# Data_Process_System.net
KiCad netlist of a schematic drawn in Altium Designer
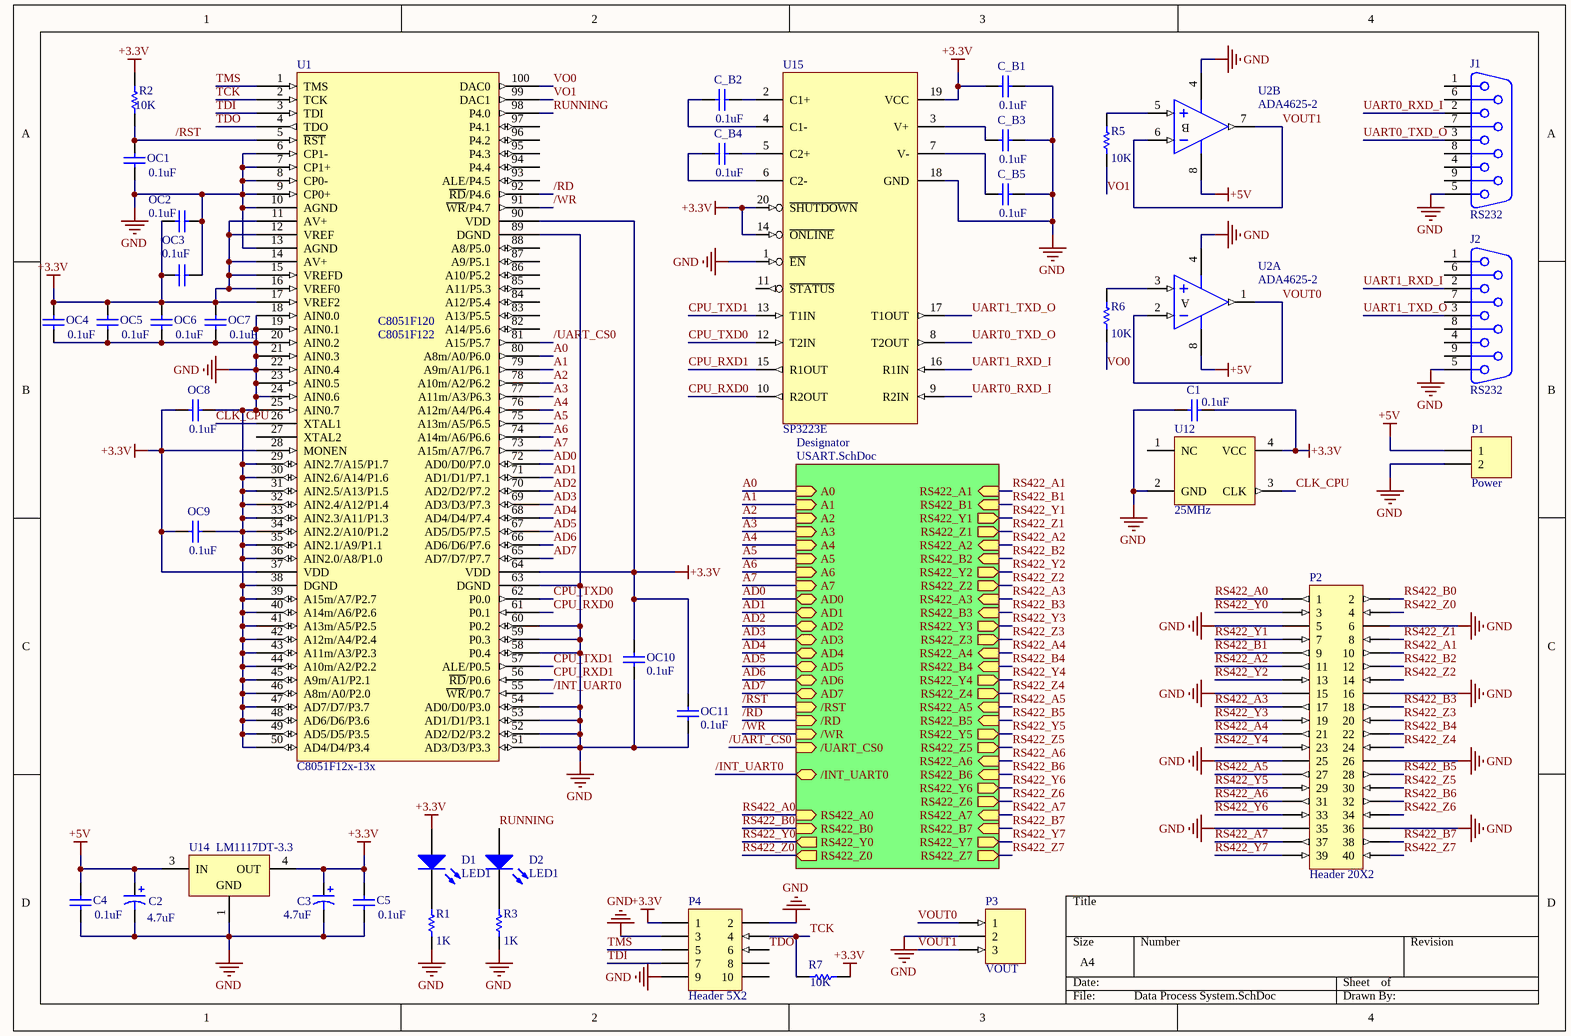
[diagram p0: Data Process System.SchDoc]

(export (version "E")
  (design (tool "Eeschema 10.0.6"))
  (components
    (comp (ref "C1")
      (value "0.1uF")
      (footprint "0805")
      (description "Capacitor")
      (fields (field (name "Comment") "Cap 0.1uf") (field (name "PUBLISHER") "Altium Limited"))
      (libsource (lib "Miscellaneous Devices") (part "Cap"))
    )
    (comp (ref "C2")
      (value "4.7uF")
      (footprint "3528")
      (description "Polarized Capacitor (Surface Mount)")
      (fields (field (name "Comment") "Cap Pol 4.7uf") (field (name "PUBLISHER") "Altium Limited"))
      (libsource (lib "Miscellaneous Devices") (part "Cap Pol3"))
    )
    (comp (ref "C3")
      (value "4.7uF")
      (footprint "3528")
      (description "Polarized Capacitor (Surface Mount)")
      (fields (field (name "Comment") "Cap Pol 4.7uf") (field (name "PUBLISHER") "Altium Limited"))
      (libsource (lib "Miscellaneous Devices") (part "Cap Pol3"))
    )
    (comp (ref "C4")
      (value "0.1uF")
      (footprint "0805")
      (description "Capacitor")
      (fields (field (name "Comment") "Cap 0.1uf") (field (name "PUBLISHER") "Altium Limited"))
      (libsource (lib "Miscellaneous Devices") (part "Cap"))
    )
    (comp (ref "C5")
      (value "0.1uF")
      (footprint "0805")
      (description "Capacitor")
      (fields (field (name "Comment") "Cap 0.1uf") (field (name "PUBLISHER") "Altium Limited"))
      (libsource (lib "Miscellaneous Devices") (part "Cap"))
    )
    (comp (ref "C_B1")
      (value "0.1uF")
      (footprint "0805")
      (description "Capacitor")
      (fields (field (name "Comment") "Cap 0.1uf") (field (name "PUBLISHER") "Altium Limited"))
      (libsource (lib "Miscellaneous Devices") (part "Cap"))
    )
    (comp (ref "C_B2")
      (value "0.1uF")
      (footprint "0805")
      (description "Capacitor")
      (fields (field (name "Comment") "Cap 0.1uf") (field (name "PUBLISHER") "Altium Limited"))
      (libsource (lib "Miscellaneous Devices") (part "Cap"))
    )
    (comp (ref "C_B3")
      (value "0.1uF")
      (footprint "0805")
      (description "Capacitor")
      (fields (field (name "Comment") "Cap 0.1uf") (field (name "PUBLISHER") "Altium Limited"))
      (libsource (lib "Miscellaneous Devices") (part "Cap"))
    )
    (comp (ref "C_B4")
      (value "0.1uF")
      (footprint "0805")
      (description "Capacitor")
      (fields (field (name "Comment") "Cap 0.1uf") (field (name "PUBLISHER") "Altium Limited"))
      (libsource (lib "Miscellaneous Devices") (part "Cap"))
    )
    (comp (ref "C_B5")
      (value "0.1uF")
      (footprint "0805")
      (description "Capacitor")
      (fields (field (name "Comment") "Cap 0.1uf") (field (name "PUBLISHER") "Altium Limited"))
      (libsource (lib "Miscellaneous Devices") (part "Cap"))
    )
    (comp (ref "D1")
      (value "LED1")
      (footprint "3216")
      (description "Typical RED GaAs LED")
      (fields (field (name "PUBLISHER") "Altium Limited"))
      (libsource (lib "Miscellaneous Devices") (part "LED1"))
    )
    (comp (ref "D2")
      (value "LED1")
      (footprint "3216")
      (description "Typical RED GaAs LED")
      (fields (field (name "PUBLISHER") "Altium Limited"))
      (libsource (lib "Miscellaneous Devices") (part "LED1"))
    )
    (comp (ref "J1")
      (value "RS232")
      (footprint "DSUB1.385-2H9")
      (description "Receptacle Assembly, 9 Position, Right Angle")
      (fields (field (name "PUBLISHER") "Altium Limited"))
      (libsource (lib "Miscellaneous Connectors") (part "D Connector 9"))
    )
    (comp (ref "J2")
      (value "RS232")
      (footprint "DSUB1.385-2H9")
      (description "Receptacle Assembly, 9 Position, Right Angle")
      (fields (field (name "PUBLISHER") "Altium Limited"))
      (libsource (lib "Miscellaneous Connectors") (part "D Connector 9"))
    )
    (comp (ref "OC1")
      (value "0.1uF")
      (footprint "0805")
      (description "Capacitor")
      (fields (field (name "Comment") "Cap 0.1uf") (field (name "PUBLISHER") "Altium Limited"))
      (libsource (lib "Miscellaneous Devices") (part "Cap"))
    )
    (comp (ref "OC2")
      (value "0.1uF")
      (footprint "0805")
      (description "Capacitor")
      (fields (field (name "Comment") "Cap 0.1uf") (field (name "PUBLISHER") "Altium Limited"))
      (libsource (lib "Miscellaneous Devices") (part "Cap"))
    )
    (comp (ref "OC3")
      (value "0.1uF")
      (footprint "0805")
      (description "Capacitor")
      (fields (field (name "Comment") "Cap 0.1uf") (field (name "PUBLISHER") "Altium Limited"))
      (libsource (lib "Miscellaneous Devices") (part "Cap"))
    )
    (comp (ref "OC4")
      (value "0.1uF")
      (footprint "0805")
      (description "Capacitor")
      (fields (field (name "Comment") "Cap 0.1uf") (field (name "PUBLISHER") "Altium Limited"))
      (libsource (lib "Miscellaneous Devices") (part "Cap"))
    )
    (comp (ref "OC5")
      (value "0.1uF")
      (footprint "0805")
      (description "Capacitor")
      (fields (field (name "Comment") "Cap 0.1uf") (field (name "PUBLISHER") "Altium Limited"))
      (libsource (lib "Miscellaneous Devices") (part "Cap"))
    )
    (comp (ref "OC6")
      (value "0.1uF")
      (footprint "0805")
      (description "Capacitor")
      (fields (field (name "Comment") "Cap 0.1uf") (field (name "PUBLISHER") "Altium Limited"))
      (libsource (lib "Miscellaneous Devices") (part "Cap"))
    )
    (comp (ref "OC7")
      (value "0.1uF")
      (footprint "0805")
      (description "Capacitor")
      (fields (field (name "Comment") "Cap 0.1uf") (field (name "PUBLISHER") "Altium Limited"))
      (libsource (lib "Miscellaneous Devices") (part "Cap"))
    )
    (comp (ref "OC8")
      (value "0.1uF")
      (footprint "0805")
      (description "Capacitor")
      (fields (field (name "Comment") "Cap 0.1uf") (field (name "PUBLISHER") "Altium Limited"))
      (libsource (lib "Miscellaneous Devices") (part "Cap"))
    )
    (comp (ref "OC9")
      (value "0.1uF")
      (footprint "0805")
      (description "Capacitor")
      (fields (field (name "Comment") "Cap 0.1uf") (field (name "PUBLISHER") "Altium Limited"))
      (libsource (lib "Miscellaneous Devices") (part "Cap"))
    )
    (comp (ref "OC10")
      (value "0.1uF")
      (footprint "0805")
      (description "Capacitor")
      (fields (field (name "Comment") "Cap 0.1uf") (field (name "PUBLISHER") "Altium Limited"))
      (libsource (lib "Miscellaneous Devices") (part "Cap"))
    )
    (comp (ref "OC11")
      (value "0.1uF")
      (footprint "0805")
      (description "Capacitor")
      (fields (field (name "Comment") "Cap 0.1uf") (field (name "PUBLISHER") "Altium Limited"))
      (libsource (lib "Miscellaneous Devices") (part "Cap"))
    )
    (comp (ref "P1")
      (value "Power")
      (footprint "HDR1X2")
      (description "Header, 2-Pin")
      (fields (field (name "PUBLISHER") "Altium Limited"))
      (libsource (lib "Miscellaneous Connectors") (part "Header 2"))
    )
    (comp (ref "P2")
      (value "Header 20X2")
      (footprint "HDR2X20")
      (description "Header, 20-Pin, Dual row")
      (fields (field (name "PUBLISHER") "Altium Limited"))
      (libsource (lib "Miscellaneous Connectors") (part "Header 20X2"))
    )
    (comp (ref "P3")
      (value "VOUT")
      (footprint "HDR1X3")
      (description "Header, 3-Pin")
      (fields (field (name "PUBLISHER") "Altium Limited"))
      (libsource (lib "Miscellaneous Connectors") (part "Header 3"))
    )
    (comp (ref "P4")
      (value "Header 5X2")
      (footprint "HDR2X5")
      (description "Header, 5-Pin, Dual row")
      (fields (field (name "PUBLISHER") "Altium Limited"))
      (libsource (lib "Miscellaneous Connectors") (part "Header 5X2"))
    )
    (comp (ref "R1")
      (value "1K")
      (footprint "0805")
      (description "Resistor")
      (fields (field (name "Comment") "1k") (field (name "PUBLISHER") "Altium Limited"))
      (libsource (lib "Miscellaneous Devices") (part "Res1"))
    )
    (comp (ref "R2")
      (value "10K")
      (footprint "0805")
      (description "Resistor")
      (fields (field (name "Comment") "10k") (field (name "PUBLISHER") "Altium Limited"))
      (libsource (lib "Miscellaneous Devices") (part "Res1"))
    )
    (comp (ref "R3")
      (value "1K")
      (footprint "0805")
      (description "Resistor")
      (fields (field (name "Comment") "1k") (field (name "PUBLISHER") "Altium Limited"))
      (libsource (lib "Miscellaneous Devices") (part "Res1"))
    )
    (comp (ref "R5")
      (value "10K")
      (footprint "0805")
      (description "Resistor")
      (fields (field (name "Comment") "10k") (field (name "PUBLISHER") "Altium Limited"))
      (libsource (lib "Miscellaneous Devices") (part "Res1"))
    )
    (comp (ref "R6")
      (value "10K")
      (footprint "0805")
      (description "Resistor")
      (fields (field (name "Comment") "10k") (field (name "PUBLISHER") "Altium Limited"))
      (libsource (lib "Miscellaneous Devices") (part "Res1"))
    )
    (comp (ref "R7")
      (value "10K")
      (footprint "0805")
      (description "Resistor")
      (fields (field (name "Comment") "10k") (field (name "PUBLISHER") "Altium Limited"))
      (libsource (lib "Miscellaneous Devices") (part "Res1"))
    )
    (comp (ref "U1")
      (value "C8051F12x-13x")
      (footprint "TSQFP50P1600X1600X120-100N")
      (libsource (lib "MyLib") (part "COMPONENT_1"))
    )
    (comp (ref "U2")
      (value "ADA4625-2")
      (footprint "SO-8_L")
      (description "Dual Low-Bias-Current Precision Operational Amplifier")
      (fields (field (name "PUBLISHER") "Altium Limited"))
      (libsource (lib "AD Operational Amplifier") (part "OP297GS"))
    )
    (comp (ref "U12")
      (value "25MHz")
      (footprint "my_SiT8103")
      (libsource (lib "cs_Schlib1") (part "my_SiT8103"))
    )
    (comp (ref "U14")
      (value "LM1117DT-3.3")
      (footprint "TD03B_N")
      (description "800mA Low-Dropout Linear Regulator, 3-pin TO-252")
      (fields
        (field (name "MANUFACTURER") "National Semiconductor")
        (field (name "PUBLISHER") "Altium Limited")
      )
      (libsource (lib "NSC LDO") (part "LM1117DT-3.3"))
    )
    (comp (ref "U15")
      (value "SP3223E")
      (footprint "SOP65P800X200-20N")
      (libsource (lib "cs_Schlib1") (part "my_SP3223E"))
    )
  )
  (nets
    (net (code "1") (name "+3.3V") (class "Default")
      (node (ref "C1") (pin "1") (pinfunction "1_1") (pintype "passive"))
      (node (ref "C3") (pin "1") (pinfunction "1_1") (pintype "passive"))
      (node (ref "C5") (pin "2") (pinfunction "2_2") (pintype "passive"))
      (node (ref "C_B1") (pin "1") (pinfunction "1_1") (pintype "passive"))
      (node (ref "D1") (pin "1") (pinfunction "A_1") (pintype "passive"))
      (node (ref "OC10") (pin "2") (pinfunction "2_2") (pintype "passive"))
      (node (ref "OC11") (pin "2") (pinfunction "2_2") (pintype "passive"))
      (node (ref "OC2") (pin "1") (pinfunction "1_1") (pintype "passive"))
      (node (ref "OC3") (pin "1") (pinfunction "1_1") (pintype "passive"))
      (node (ref "OC4") (pin "2") (pinfunction "2_2") (pintype "passive"))
      (node (ref "OC5") (pin "2") (pinfunction "2_2") (pintype "passive"))
      (node (ref "OC6") (pin "2") (pinfunction "2_2") (pintype "passive"))
      (node (ref "OC7") (pin "2") (pinfunction "2_2") (pintype "passive"))
      (node (ref "OC8") (pin "1") (pinfunction "1_1") (pintype "passive"))
      (node (ref "OC9") (pin "1") (pinfunction "1_1") (pintype "passive"))
      (node (ref "P4") (pin "1") (pinfunction "1_1") (pintype "passive"))
      (node (ref "R2") (pin "2") (pinfunction "2_2") (pintype "passive"))
      (node (ref "R7") (pin "2") (pinfunction "2_2") (pintype "passive"))
      (node (ref "U1") (pin "11") (pinfunction "AV+_11") (pintype "power_in"))
      (node (ref "U1") (pin "12") (pinfunction "VREF_12") (pintype "passive"))
      (node (ref "U1") (pin "14") (pinfunction "AV+_14") (pintype "power_in"))
      (node (ref "U1") (pin "15") (pinfunction "VREFD_15") (pintype "input"))
      (node (ref "U1") (pin "16") (pinfunction "VREF0_16") (pintype "input"))
      (node (ref "U1") (pin "17") (pinfunction "VREF2_17") (pintype "input"))
      (node (ref "U1") (pin "28") (pinfunction "MONEN_28") (pintype "input"))
      (node (ref "U1") (pin "37") (pinfunction "VDD_37") (pintype "power_in"))
      (node (ref "U1") (pin "64") (pinfunction "VDD_64") (pintype "power_in"))
      (node (ref "U1") (pin "90") (pinfunction "VDD_90") (pintype "power_in"))
      (node (ref "U12") (pin "4") (pinfunction "VCC_4") (pintype "power_in"))
      (node (ref "U14") (pin "4") (pinfunction "OUT_4") (pintype "power_in"))
      (node (ref "U15") (pin "14") (pinfunction "~{ONLINE}_14") (pintype "input"))
      (node (ref "U15") (pin "19") (pinfunction "VCC_19") (pintype "power_in"))
      (node (ref "U15") (pin "20") (pinfunction "~{SHUTDOWN}_20") (pintype "input"))
    )
    (net (code "2") (name "+5V") (class "Default")
      (node (ref "C2") (pin "1") (pinfunction "1_1") (pintype "passive"))
      (node (ref "C4") (pin "2") (pinfunction "2_2") (pintype "passive"))
      (node (ref "P1") (pin "1") (pinfunction "1_1") (pintype "passive"))
      (node (ref "U14") (pin "3") (pinfunction "IN_3") (pintype "power_in"))
      (node (ref "U2") (pin "8") (pinfunction "V+_8") (pintype "power_in"))
    )
    (net (code "3") (name "/A0") (class "Default")
      (node (ref "U1") (pin "80") (pinfunction "A8m/A0/P6.0_80") (pintype "output"))
    )
    (net (code "4") (name "/A1") (class "Default")
      (node (ref "U1") (pin "79") (pinfunction "A9m/A1/P6.1_79") (pintype "output"))
    )
    (net (code "5") (name "/A2") (class "Default")
      (node (ref "U1") (pin "78") (pinfunction "A10m/A2/P6.2_78") (pintype "output"))
    )
    (net (code "6") (name "/A3") (class "Default")
      (node (ref "U1") (pin "77") (pinfunction "A11m/A3/P6.3_77") (pintype "output"))
    )
    (net (code "7") (name "/A4") (class "Default")
      (node (ref "U1") (pin "76") (pinfunction "A12m/A4/P6.4_76") (pintype "output"))
    )
    (net (code "8") (name "/A5") (class "Default")
      (node (ref "U1") (pin "75") (pinfunction "A13m/A5/P6.5_75") (pintype "output"))
    )
    (net (code "9") (name "/A6") (class "Default")
      (node (ref "U1") (pin "74") (pinfunction "A14m/A6/P6.6_74") (pintype "output"))
    )
    (net (code "10") (name "/A7") (class "Default")
      (node (ref "U1") (pin "73") (pinfunction "A15m/A7/P6.7_73") (pintype "output"))
    )
    (net (code "11") (name "/AD0") (class "Default")
      (node (ref "U1") (pin "72") (pinfunction "AD0/D0/P7.0_72") (pintype "bidirectional"))
    )
    (net (code "12") (name "/AD1") (class "Default")
      (node (ref "U1") (pin "71") (pinfunction "AD1/D1/P7.1_71") (pintype "bidirectional"))
    )
    (net (code "13") (name "/AD2") (class "Default")
      (node (ref "U1") (pin "70") (pinfunction "AD2/D2/P7.2_70") (pintype "bidirectional"))
    )
    (net (code "14") (name "/AD3") (class "Default")
      (node (ref "U1") (pin "69") (pinfunction "AD3/D3/P7.3_69") (pintype "bidirectional"))
    )
    (net (code "15") (name "/AD4") (class "Default")
      (node (ref "U1") (pin "68") (pinfunction "AD4/D4/P7.4_68") (pintype "bidirectional"))
    )
    (net (code "16") (name "/AD5") (class "Default")
      (node (ref "U1") (pin "67") (pinfunction "AD5/D5/P7.5_67") (pintype "bidirectional"))
    )
    (net (code "17") (name "/AD6") (class "Default")
      (node (ref "U1") (pin "66") (pinfunction "AD6/D6/P7.6_66") (pintype "bidirectional"))
    )
    (net (code "18") (name "/AD7") (class "Default")
      (node (ref "U1") (pin "65") (pinfunction "AD7/D7/P7.7_65") (pintype "bidirectional"))
    )
    (net (code "19") (name "/CLK_CPU") (class "Default")
      (node (ref "U1") (pin "26") (pinfunction "XTAL1_26") (pintype "passive"))
      (node (ref "U12") (pin "3") (pinfunction "CLK_3") (pintype "output"))
    )
    (net (code "20") (name "/CPU_RXD0") (class "Default")
      (node (ref "U1") (pin "61") (pinfunction "P0.1_61") (pintype "input"))
      (node (ref "U15") (pin "10") (pinfunction "R2OUT_10") (pintype "output"))
    )
    (net (code "21") (name "/CPU_RXD1") (class "Default")
      (node (ref "U1") (pin "56") (pinfunction "~{RD}/P0.6_56") (pintype "input"))
      (node (ref "U15") (pin "15") (pinfunction "R1OUT_15") (pintype "output"))
    )
    (net (code "22") (name "/CPU_TXD0") (class "Default")
      (node (ref "U1") (pin "62") (pinfunction "P0.0_62") (pintype "output"))
      (node (ref "U15") (pin "12") (pinfunction "T2IN_12") (pintype "input"))
    )
    (net (code "23") (name "/CPU_TXD1") (class "Default")
      (node (ref "U1") (pin "57") (pinfunction "ALE/P0.5_57") (pintype "output"))
      (node (ref "U15") (pin "13") (pinfunction "T1IN_13") (pintype "input"))
    )
    (net (code "24") (name "/RS422_A0") (class "Default")
      (node (ref "P2") (pin "1") (pinfunction "1_1") (pintype "output"))
    )
    (net (code "25") (name "/RS422_A1") (class "Default")
      (node (ref "P2") (pin "10") (pinfunction "10_10") (pintype "output"))
    )
    (net (code "26") (name "/RS422_A2") (class "Default")
      (node (ref "P2") (pin "11") (pinfunction "11_11") (pintype "output"))
    )
    (net (code "27") (name "/RS422_A3") (class "Default")
      (node (ref "P2") (pin "17") (pinfunction "17_17") (pintype "output"))
    )
    (net (code "28") (name "/RS422_A4") (class "Default")
      (node (ref "P2") (pin "21") (pinfunction "21_21") (pintype "output"))
    )
    (net (code "29") (name "/RS422_A5") (class "Default")
      (node (ref "P2") (pin "27") (pinfunction "27_27") (pintype "output"))
    )
    (net (code "30") (name "/RS422_A6") (class "Default")
      (node (ref "P2") (pin "31") (pinfunction "31_31") (pintype "output"))
    )
    (net (code "31") (name "/RS422_A7") (class "Default")
      (node (ref "P2") (pin "37") (pinfunction "37_37") (pintype "output"))
    )
    (net (code "32") (name "/RS422_B0") (class "Default")
      (node (ref "P2") (pin "2") (pinfunction "2_2") (pintype "output"))
    )
    (net (code "33") (name "/RS422_B1") (class "Default")
      (node (ref "P2") (pin "9") (pinfunction "9_9") (pintype "output"))
    )
    (net (code "34") (name "/RS422_B2") (class "Default")
      (node (ref "P2") (pin "12") (pinfunction "12_12") (pintype "output"))
    )
    (net (code "35") (name "/RS422_B3") (class "Default")
      (node (ref "P2") (pin "18") (pinfunction "18_18") (pintype "output"))
    )
    (net (code "36") (name "/RS422_B4") (class "Default")
      (node (ref "P2") (pin "22") (pinfunction "22_22") (pintype "output"))
    )
    (net (code "37") (name "/RS422_B5") (class "Default")
      (node (ref "P2") (pin "28") (pinfunction "28_28") (pintype "output"))
    )
    (net (code "38") (name "/RS422_B6") (class "Default")
      (node (ref "P2") (pin "32") (pinfunction "32_32") (pintype "output"))
    )
    (net (code "39") (name "/RS422_B7") (class "Default")
      (node (ref "P2") (pin "38") (pinfunction "38_38") (pintype "output"))
    )
    (net (code "40") (name "/RS422_Y0") (class "Default")
      (node (ref "P2") (pin "3") (pinfunction "3_3") (pintype "input"))
    )
    (net (code "41") (name "/RS422_Y1") (class "Default")
      (node (ref "P2") (pin "7") (pinfunction "7_7") (pintype "input"))
    )
    (net (code "42") (name "/RS422_Y2") (class "Default")
      (node (ref "P2") (pin "13") (pinfunction "13_13") (pintype "input"))
    )
    (net (code "43") (name "/RS422_Y3") (class "Default")
      (node (ref "P2") (pin "19") (pinfunction "19_19") (pintype "input"))
    )
    (net (code "44") (name "/RS422_Y4") (class "Default")
      (node (ref "P2") (pin "23") (pinfunction "23_23") (pintype "input"))
    )
    (net (code "45") (name "/RS422_Y5") (class "Default")
      (node (ref "P2") (pin "29") (pinfunction "29_29") (pintype "input"))
    )
    (net (code "46") (name "/RS422_Y6") (class "Default")
      (node (ref "P2") (pin "33") (pinfunction "33_33") (pintype "input"))
    )
    (net (code "47") (name "/RS422_Y7") (class "Default")
      (node (ref "P2") (pin "39") (pinfunction "39_39") (pintype "input"))
    )
    (net (code "48") (name "/RS422_Z0") (class "Default")
      (node (ref "P2") (pin "4") (pinfunction "4_4") (pintype "input"))
    )
    (net (code "49") (name "/RS422_Z1") (class "Default")
      (node (ref "P2") (pin "8") (pinfunction "8_8") (pintype "input"))
    )
    (net (code "50") (name "/RS422_Z2") (class "Default")
      (node (ref "P2") (pin "14") (pinfunction "14_14") (pintype "input"))
    )
    (net (code "51") (name "/RS422_Z3") (class "Default")
      (node (ref "P2") (pin "20") (pinfunction "20_20") (pintype "input"))
    )
    (net (code "52") (name "/RS422_Z4") (class "Default")
      (node (ref "P2") (pin "24") (pinfunction "24_24") (pintype "input"))
    )
    (net (code "53") (name "/RS422_Z5") (class "Default")
      (node (ref "P2") (pin "30") (pinfunction "30_30") (pintype "input"))
    )
    (net (code "54") (name "/RS422_Z6") (class "Default")
      (node (ref "P2") (pin "34") (pinfunction "34_34") (pintype "input"))
    )
    (net (code "55") (name "/RS422_Z7") (class "Default")
      (node (ref "P2") (pin "40") (pinfunction "40_40") (pintype "input"))
    )
    (net (code "56") (name "/RUNNING") (class "Default")
      (node (ref "D2") (pin "1") (pinfunction "A_1") (pintype "passive"))
      (node (ref "U1") (pin "98") (pinfunction "P4.0_98") (pintype "output"))
    )
    (net (code "57") (name "/TCK") (class "Default")
      (node (ref "P4") (pin "4") (pinfunction "4_4") (pintype "input"))
      (node (ref "R7") (pin "1") (pinfunction "1_1") (pintype "passive"))
      (node (ref "U1") (pin "2") (pinfunction "TCK_2") (pintype "input"))
    )
    (net (code "58") (name "/TDI") (class "Default")
      (node (ref "P4") (pin "7") (pinfunction "7_7") (pintype "passive"))
      (node (ref "U1") (pin "3") (pinfunction "TDI_3") (pintype "input"))
    )
    (net (code "59") (name "/TDO") (class "Default")
      (node (ref "P4") (pin "6") (pinfunction "6_6") (pintype "input"))
      (node (ref "U1") (pin "4") (pinfunction "TDO_4") (pintype "output"))
    )
    (net (code "60") (name "/TMS") (class "Default")
      (node (ref "P4") (pin "5") (pinfunction "5_5") (pintype "passive"))
      (node (ref "U1") (pin "1") (pinfunction "TMS_1") (pintype "input"))
    )
    (net (code "61") (name "/UART0_RXD_I") (class "Default")
      (node (ref "J1") (pin "2") (pinfunction "2_2") (pintype "passive"))
      (node (ref "U15") (pin "9") (pinfunction "R2IN_9") (pintype "input"))
    )
    (net (code "62") (name "/UART0_TXD_O") (class "Default")
      (node (ref "J1") (pin "3") (pinfunction "3_3") (pintype "passive"))
      (node (ref "U15") (pin "8") (pinfunction "T2OUT_8") (pintype "output"))
    )
    (net (code "63") (name "/UART1_RXD_I") (class "Default")
      (node (ref "J2") (pin "2") (pinfunction "2_2") (pintype "passive"))
      (node (ref "U15") (pin "16") (pinfunction "R1IN_16") (pintype "input"))
    )
    (net (code "64") (name "/UART1_TXD_O") (class "Default")
      (node (ref "J2") (pin "3") (pinfunction "3_3") (pintype "passive"))
      (node (ref "U15") (pin "17") (pinfunction "T1OUT_17") (pintype "output"))
    )
    (net (code "65") (name "/VO0") (class "Default")
      (node (ref "R6") (pin "2") (pinfunction "2_2") (pintype "passive"))
      (node (ref "U1") (pin "100") (pinfunction "DAC0_100") (pintype "output"))
    )
    (net (code "66") (name "/VO1") (class "Default")
      (node (ref "R5") (pin "2") (pinfunction "2_2") (pintype "passive"))
      (node (ref "U1") (pin "99") (pinfunction "DAC1_99") (pintype "output"))
    )
    (net (code "67") (name "/VOUT0") (class "Default")
      (node (ref "P3") (pin "1") (pinfunction "1_1") (pintype "input"))
      (node (ref "U2") (pin "1") (pinfunction "OUT_1") (pintype "output"))
      (node (ref "U2") (pin "2") (pinfunction "IN-_2") (pintype "input"))
    )
    (net (code "68") (name "/VOUT1") (class "Default")
      (node (ref "P3") (pin "3") (pinfunction "3_3") (pintype "input"))
      (node (ref "U2") (pin "6") (pinfunction "IN-_6") (pintype "input"))
      (node (ref "U2") (pin "7") (pinfunction "OUT_7") (pintype "output"))
    )
    (net (code "69") (name "/{slash}INT_UART0") (class "Default")
      (node (ref "U1") (pin "55") (pinfunction "~{WR}/P0.7_55") (pintype "input"))
    )
    (net (code "70") (name "/{slash}RD") (class "Default")
      (node (ref "U1") (pin "92") (pinfunction "~{RD}/P4.6_92") (pintype "output"))
    )
    (net (code "71") (name "/{slash}RST") (class "Default")
      (node (ref "OC1") (pin "2") (pinfunction "2_2") (pintype "passive"))
      (node (ref "R2") (pin "1") (pinfunction "1_1") (pintype "passive"))
      (node (ref "U1") (pin "5") (pinfunction "~{RST}_5") (pintype "input"))
    )
    (net (code "72") (name "/{slash}UART_CS0") (class "Default")
      (node (ref "U1") (pin "81") (pinfunction "A15/P5.7_81") (pintype "output"))
    )
    (net (code "73") (name "/{slash}WR") (class "Default")
      (node (ref "U1") (pin "91") (pinfunction "~{WR}/P4.7_91") (pintype "output"))
    )
    (net (code "74") (name "GND") (class "Default")
      (node (ref "C1") (pin "2") (pinfunction "2_2") (pintype "passive"))
      (node (ref "C2") (pin "2") (pinfunction "2_2") (pintype "passive"))
      (node (ref "C3") (pin "2") (pinfunction "2_2") (pintype "passive"))
      (node (ref "C4") (pin "1") (pinfunction "1_1") (pintype "passive"))
      (node (ref "C5") (pin "1") (pinfunction "1_1") (pintype "passive"))
      (node (ref "C_B1") (pin "2") (pinfunction "2_2") (pintype "passive"))
      (node (ref "C_B3") (pin "2") (pinfunction "2_2") (pintype "passive"))
      (node (ref "C_B5") (pin "2") (pinfunction "2_2") (pintype "passive"))
      (node (ref "J1") (pin "5") (pinfunction "5_5") (pintype "passive"))
      (node (ref "J2") (pin "5") (pinfunction "5_5") (pintype "passive"))
      (node (ref "OC1") (pin "1") (pinfunction "1_1") (pintype "passive"))
      (node (ref "OC10") (pin "1") (pinfunction "1_1") (pintype "passive"))
      (node (ref "OC11") (pin "1") (pinfunction "1_1") (pintype "passive"))
      (node (ref "OC2") (pin "2") (pinfunction "2_2") (pintype "passive"))
      (node (ref "OC3") (pin "2") (pinfunction "2_2") (pintype "passive"))
      (node (ref "OC4") (pin "1") (pinfunction "1_1") (pintype "passive"))
      (node (ref "OC5") (pin "1") (pinfunction "1_1") (pintype "passive"))
      (node (ref "OC6") (pin "1") (pinfunction "1_1") (pintype "passive"))
      (node (ref "OC7") (pin "1") (pinfunction "1_1") (pintype "passive"))
      (node (ref "OC8") (pin "2") (pinfunction "2_2") (pintype "passive"))
      (node (ref "OC9") (pin "2") (pinfunction "2_2") (pintype "passive"))
      (node (ref "P1") (pin "2") (pinfunction "2_2") (pintype "passive"))
      (node (ref "P2") (pin "15") (pinfunction "15_15") (pintype "power_in"))
      (node (ref "P2") (pin "16") (pinfunction "16_16") (pintype "power_in"))
      (node (ref "P2") (pin "25") (pinfunction "25_25") (pintype "power_in"))
      (node (ref "P2") (pin "26") (pinfunction "26_26") (pintype "power_in"))
      (node (ref "P2") (pin "35") (pinfunction "35_35") (pintype "power_in"))
      (node (ref "P2") (pin "36") (pinfunction "36_36") (pintype "power_in"))
      (node (ref "P2") (pin "5") (pinfunction "5_5") (pintype "power_in"))
      (node (ref "P2") (pin "6") (pinfunction "6_6") (pintype "power_in"))
      (node (ref "P3") (pin "2") (pinfunction "2_2") (pintype "passive"))
      (node (ref "P4") (pin "2") (pinfunction "2_2") (pintype "passive"))
      (node (ref "P4") (pin "3") (pinfunction "3_3") (pintype "passive"))
      (node (ref "P4") (pin "9") (pinfunction "9_9") (pintype "passive"))
      (node (ref "R1") (pin "1") (pinfunction "1_1") (pintype "passive"))
      (node (ref "R3") (pin "1") (pinfunction "1_1") (pintype "passive"))
      (node (ref "U1") (pin "10") (pinfunction "AGND_10") (pintype "power_in"))
      (node (ref "U1") (pin "13") (pinfunction "AGND_13") (pintype "power_in"))
      (node (ref "U1") (pin "18") (pinfunction "AIN0.0_18") (pintype "input"))
      (node (ref "U1") (pin "19") (pinfunction "AIN0.1_19") (pintype "input"))
      (node (ref "U1") (pin "20") (pinfunction "AIN0.2_20") (pintype "input"))
      (node (ref "U1") (pin "21") (pinfunction "AIN0.3_21") (pintype "input"))
      (node (ref "U1") (pin "22") (pinfunction "AIN0.4_22") (pintype "input"))
      (node (ref "U1") (pin "23") (pinfunction "AIN0.5_23") (pintype "input"))
      (node (ref "U1") (pin "24") (pinfunction "AIN0.6_24") (pintype "input"))
      (node (ref "U1") (pin "25") (pinfunction "AIN0.7_25") (pintype "input"))
      (node (ref "U1") (pin "29") (pinfunction "AIN2.7/A15/P1.7_29") (pintype "bidirectional"))
      (node (ref "U1") (pin "30") (pinfunction "AIN2.6/A14/P1.6_30") (pintype "bidirectional"))
      (node (ref "U1") (pin "31") (pinfunction "AIN2.5/A13/P1.5_31") (pintype "bidirectional"))
      (node (ref "U1") (pin "32") (pinfunction "AIN2.4/A12/P1.4_32") (pintype "bidirectional"))
      (node (ref "U1") (pin "33") (pinfunction "AIN2.3/A11/P1.3_33") (pintype "bidirectional"))
      (node (ref "U1") (pin "34") (pinfunction "AIN2.2/A10/P1.2_34") (pintype "bidirectional"))
      (node (ref "U1") (pin "35") (pinfunction "AIN2.1/A9/P1.1_35") (pintype "bidirectional"))
      (node (ref "U1") (pin "36") (pinfunction "AIN2.0/A8/P1.0_36") (pintype "bidirectional"))
      (node (ref "U1") (pin "38") (pinfunction "DGND_38") (pintype "power_in"))
      (node (ref "U1") (pin "39") (pinfunction "A15m/A7/P2.7_39") (pintype "bidirectional"))
      (node (ref "U1") (pin "40") (pinfunction "A14m/A6/P2.6_40") (pintype "bidirectional"))
      (node (ref "U1") (pin "41") (pinfunction "A13m/A5/P2.5_41") (pintype "bidirectional"))
      (node (ref "U1") (pin "42") (pinfunction "A12m/A4/P2.4_42") (pintype "bidirectional"))
      (node (ref "U1") (pin "43") (pinfunction "A11m/A3/P2.3_43") (pintype "bidirectional"))
      (node (ref "U1") (pin "44") (pinfunction "A10m/A2/P2.2_44") (pintype "bidirectional"))
      (node (ref "U1") (pin "45") (pinfunction "A9m/A1/P2.1_45") (pintype "bidirectional"))
      (node (ref "U1") (pin "46") (pinfunction "A8m/A0/P2.0_46") (pintype "bidirectional"))
      (node (ref "U1") (pin "47") (pinfunction "AD7/D7/P3.7_47") (pintype "bidirectional"))
      (node (ref "U1") (pin "48") (pinfunction "AD6/D6/P3.6_48") (pintype "bidirectional"))
      (node (ref "U1") (pin "49") (pinfunction "AD5/D5/P3.5_49") (pintype "bidirectional"))
      (node (ref "U1") (pin "50") (pinfunction "AD4/D4/P3.4_50") (pintype "bidirectional"))
      (node (ref "U1") (pin "51") (pinfunction "AD3/D3/P3.3_51") (pintype "bidirectional"))
      (node (ref "U1") (pin "52") (pinfunction "AD2/D2/P3.2_52") (pintype "bidirectional"))
      (node (ref "U1") (pin "53") (pinfunction "AD1/D1/P3.1_53") (pintype "bidirectional"))
      (node (ref "U1") (pin "54") (pinfunction "AD0/D0/P3.0_54") (pintype "bidirectional"))
      (node (ref "U1") (pin "58") (pinfunction "P0.4_58") (pintype "bidirectional"))
      (node (ref "U1") (pin "59") (pinfunction "P0.3_59") (pintype "bidirectional"))
      (node (ref "U1") (pin "6") (pinfunction "CP1-_6") (pintype "input"))
      (node (ref "U1") (pin "60") (pinfunction "P0.2_60") (pintype "bidirectional"))
      (node (ref "U1") (pin "63") (pinfunction "DGND_63") (pintype "power_in"))
      (node (ref "U1") (pin "7") (pinfunction "CP1+_7") (pintype "input"))
      (node (ref "U1") (pin "8") (pinfunction "CP0-_8") (pintype "input"))
      (node (ref "U1") (pin "89") (pinfunction "DGND_89") (pintype "power_in"))
      (node (ref "U1") (pin "9") (pinfunction "CP0+_9") (pintype "input"))
      (node (ref "U12") (pin "2") (pinfunction "GND_2") (pintype "power_in"))
      (node (ref "U14") (pin "1") (pinfunction "GND_1") (pintype "power_in"))
      (node (ref "U15") (pin "1") (pinfunction "~{EN}_1") (pintype "input"))
      (node (ref "U15") (pin "18") (pinfunction "GND_18") (pintype "power_in"))
      (node (ref "U2") (pin "4") (pinfunction "V-_4") (pintype "power_in"))
    )
    (net (code "75") (name "Net-(D1-K)") (class "Default")
      (node (ref "D1") (pin "2") (pinfunction "K_2") (pintype "passive"))
      (node (ref "R1") (pin "2") (pinfunction "2_2") (pintype "passive"))
    )
    (net (code "76") (name "Net-(D2-K)") (class "Default")
      (node (ref "D2") (pin "2") (pinfunction "K_2") (pintype "passive"))
      (node (ref "R3") (pin "2") (pinfunction "2_2") (pintype "passive"))
    )
    (net (code "77") (name "Net-(U2A-IN+)") (class "Default")
      (node (ref "R6") (pin "1") (pinfunction "1_1") (pintype "passive"))
      (node (ref "U2") (pin "3") (pinfunction "IN+_3") (pintype "input"))
    )
    (net (code "78") (name "Net-(U2B-IN+)") (class "Default")
      (node (ref "R5") (pin "1") (pinfunction "1_1") (pintype "passive"))
      (node (ref "U2") (pin "5") (pinfunction "IN+_5") (pintype "input"))
    )
    (net (code "79") (name "Net-(U15-C1+)") (class "Default")
      (node (ref "C_B2") (pin "2") (pinfunction "2_2") (pintype "passive"))
      (node (ref "U15") (pin "2") (pinfunction "C1+_2") (pintype "passive"))
    )
    (net (code "80") (name "Net-(U15-C1-)") (class "Default")
      (node (ref "C_B2") (pin "1") (pinfunction "1_1") (pintype "passive"))
      (node (ref "U15") (pin "4") (pinfunction "C1-_4") (pintype "passive"))
    )
    (net (code "81") (name "Net-(U15-C2+)") (class "Default")
      (node (ref "C_B4") (pin "2") (pinfunction "2_2") (pintype "passive"))
      (node (ref "U15") (pin "5") (pinfunction "C2+_5") (pintype "passive"))
    )
    (net (code "82") (name "Net-(U15-C2-)") (class "Default")
      (node (ref "C_B4") (pin "1") (pinfunction "1_1") (pintype "passive"))
      (node (ref "U15") (pin "6") (pinfunction "C2-_6") (pintype "passive"))
    )
    (net (code "83") (name "Net-(U15-V+)") (class "Default")
      (node (ref "C_B3") (pin "1") (pinfunction "1_1") (pintype "passive"))
      (node (ref "U15") (pin "3") (pinfunction "V+_3") (pintype "passive"))
    )
    (net (code "84") (name "Net-(U15-V-)") (class "Default")
      (node (ref "C_B5") (pin "1") (pinfunction "1_1") (pintype "passive"))
      (node (ref "U15") (pin "7") (pinfunction "V-_7") (pintype "passive"))
    )
    (net (code "85") (name "unconnected-(J1-Pad1)") (class "Default")
      (node (ref "J1") (pin "1") (pinfunction "1_1") (pintype "passive"))
    )
    (net (code "86") (name "unconnected-(J1-Pad4)") (class "Default")
      (node (ref "J1") (pin "4") (pinfunction "4_4") (pintype "passive"))
    )
    (net (code "87") (name "unconnected-(J1-Pad6)") (class "Default")
      (node (ref "J1") (pin "6") (pinfunction "6_6") (pintype "passive"))
    )
    (net (code "88") (name "unconnected-(J1-Pad7)") (class "Default")
      (node (ref "J1") (pin "7") (pinfunction "7_7") (pintype "passive"))
    )
    (net (code "89") (name "unconnected-(J1-Pad8)") (class "Default")
      (node (ref "J1") (pin "8") (pinfunction "8_8") (pintype "passive"))
    )
    (net (code "90") (name "unconnected-(J1-Pad9)") (class "Default")
      (node (ref "J1") (pin "9") (pinfunction "9_9") (pintype "passive"))
    )
    (net (code "91") (name "unconnected-(J2-Pad1)") (class "Default")
      (node (ref "J2") (pin "1") (pinfunction "1_1") (pintype "passive"))
    )
    (net (code "92") (name "unconnected-(J2-Pad4)") (class "Default")
      (node (ref "J2") (pin "4") (pinfunction "4_4") (pintype "passive"))
    )
    (net (code "93") (name "unconnected-(J2-Pad6)") (class "Default")
      (node (ref "J2") (pin "6") (pinfunction "6_6") (pintype "passive"))
    )
    (net (code "94") (name "unconnected-(J2-Pad7)") (class "Default")
      (node (ref "J2") (pin "7") (pinfunction "7_7") (pintype "passive"))
    )
    (net (code "95") (name "unconnected-(J2-Pad8)") (class "Default")
      (node (ref "J2") (pin "8") (pinfunction "8_8") (pintype "passive"))
    )
    (net (code "96") (name "unconnected-(J2-Pad9)") (class "Default")
      (node (ref "J2") (pin "9") (pinfunction "9_9") (pintype "passive"))
    )
    (net (code "97") (name "unconnected-(P4-Pad8)") (class "Default")
      (node (ref "P4") (pin "8") (pinfunction "8_8") (pintype "passive"))
    )
    (net (code "98") (name "unconnected-(P4-Pad10)") (class "Default")
      (node (ref "P4") (pin "10") (pinfunction "10_10") (pintype "passive"))
    )
    (net (code "99") (name "unconnected-(U1-A8{slash}P5.0-Pad88)") (class "Default")
      (node (ref "U1") (pin "88") (pinfunction "A8/P5.0_88") (pintype "bidirectional"))
    )
    (net (code "100") (name "unconnected-(U1-A9{slash}P5.1-Pad87)") (class "Default")
      (node (ref "U1") (pin "87") (pinfunction "A9/P5.1_87") (pintype "bidirectional"))
    )
    (net (code "101") (name "unconnected-(U1-A10{slash}P5.2-Pad86)") (class "Default")
      (node (ref "U1") (pin "86") (pinfunction "A10/P5.2_86") (pintype "bidirectional"))
    )
    (net (code "102") (name "unconnected-(U1-A11{slash}P5.3-Pad85)") (class "Default")
      (node (ref "U1") (pin "85") (pinfunction "A11/P5.3_85") (pintype "bidirectional"))
    )
    (net (code "103") (name "unconnected-(U1-A12{slash}P5.4-Pad84)") (class "Default")
      (node (ref "U1") (pin "84") (pinfunction "A12/P5.4_84") (pintype "bidirectional"))
    )
    (net (code "104") (name "unconnected-(U1-A13{slash}P5.5-Pad83)") (class "Default")
      (node (ref "U1") (pin "83") (pinfunction "A13/P5.5_83") (pintype "bidirectional"))
    )
    (net (code "105") (name "unconnected-(U1-A14{slash}P5.6-Pad82)") (class "Default")
      (node (ref "U1") (pin "82") (pinfunction "A14/P5.6_82") (pintype "bidirectional"))
    )
    (net (code "106") (name "unconnected-(U1-ALE{slash}P4.5-Pad93)") (class "Default")
      (node (ref "U1") (pin "93") (pinfunction "ALE/P4.5_93") (pintype "bidirectional"))
    )
    (net (code "107") (name "unconnected-(U1-P4.1-Pad97)") (class "Default")
      (node (ref "U1") (pin "97") (pinfunction "P4.1_97") (pintype "bidirectional"))
    )
    (net (code "108") (name "unconnected-(U1-P4.2-Pad96)") (class "Default")
      (node (ref "U1") (pin "96") (pinfunction "P4.2_96") (pintype "bidirectional"))
    )
    (net (code "109") (name "unconnected-(U1-P4.3-Pad95)") (class "Default")
      (node (ref "U1") (pin "95") (pinfunction "P4.3_95") (pintype "bidirectional"))
    )
    (net (code "110") (name "unconnected-(U1-P4.4-Pad94)") (class "Default")
      (node (ref "U1") (pin "94") (pinfunction "P4.4_94") (pintype "bidirectional"))
    )
    (net (code "111") (name "unconnected-(U1-XTAL2-Pad27)") (class "Default")
      (node (ref "U1") (pin "27") (pinfunction "XTAL2_27") (pintype "passive"))
    )
    (net (code "112") (name "unconnected-(U12-NC-Pad1)") (class "Default")
      (node (ref "U12") (pin "1") (pinfunction "NC_1") (pintype "passive"))
    )
    (net (code "113") (name "unconnected-(U15-~{STATUS}-Pad11)") (class "Default")
      (node (ref "U15") (pin "11") (pinfunction "~{STATUS}_11") (pintype "output"))
    )
  )
)
